# MotorBoardPrototyp4_polyfuse.net
KiCad netlist of a schematic drawn in EAGLE
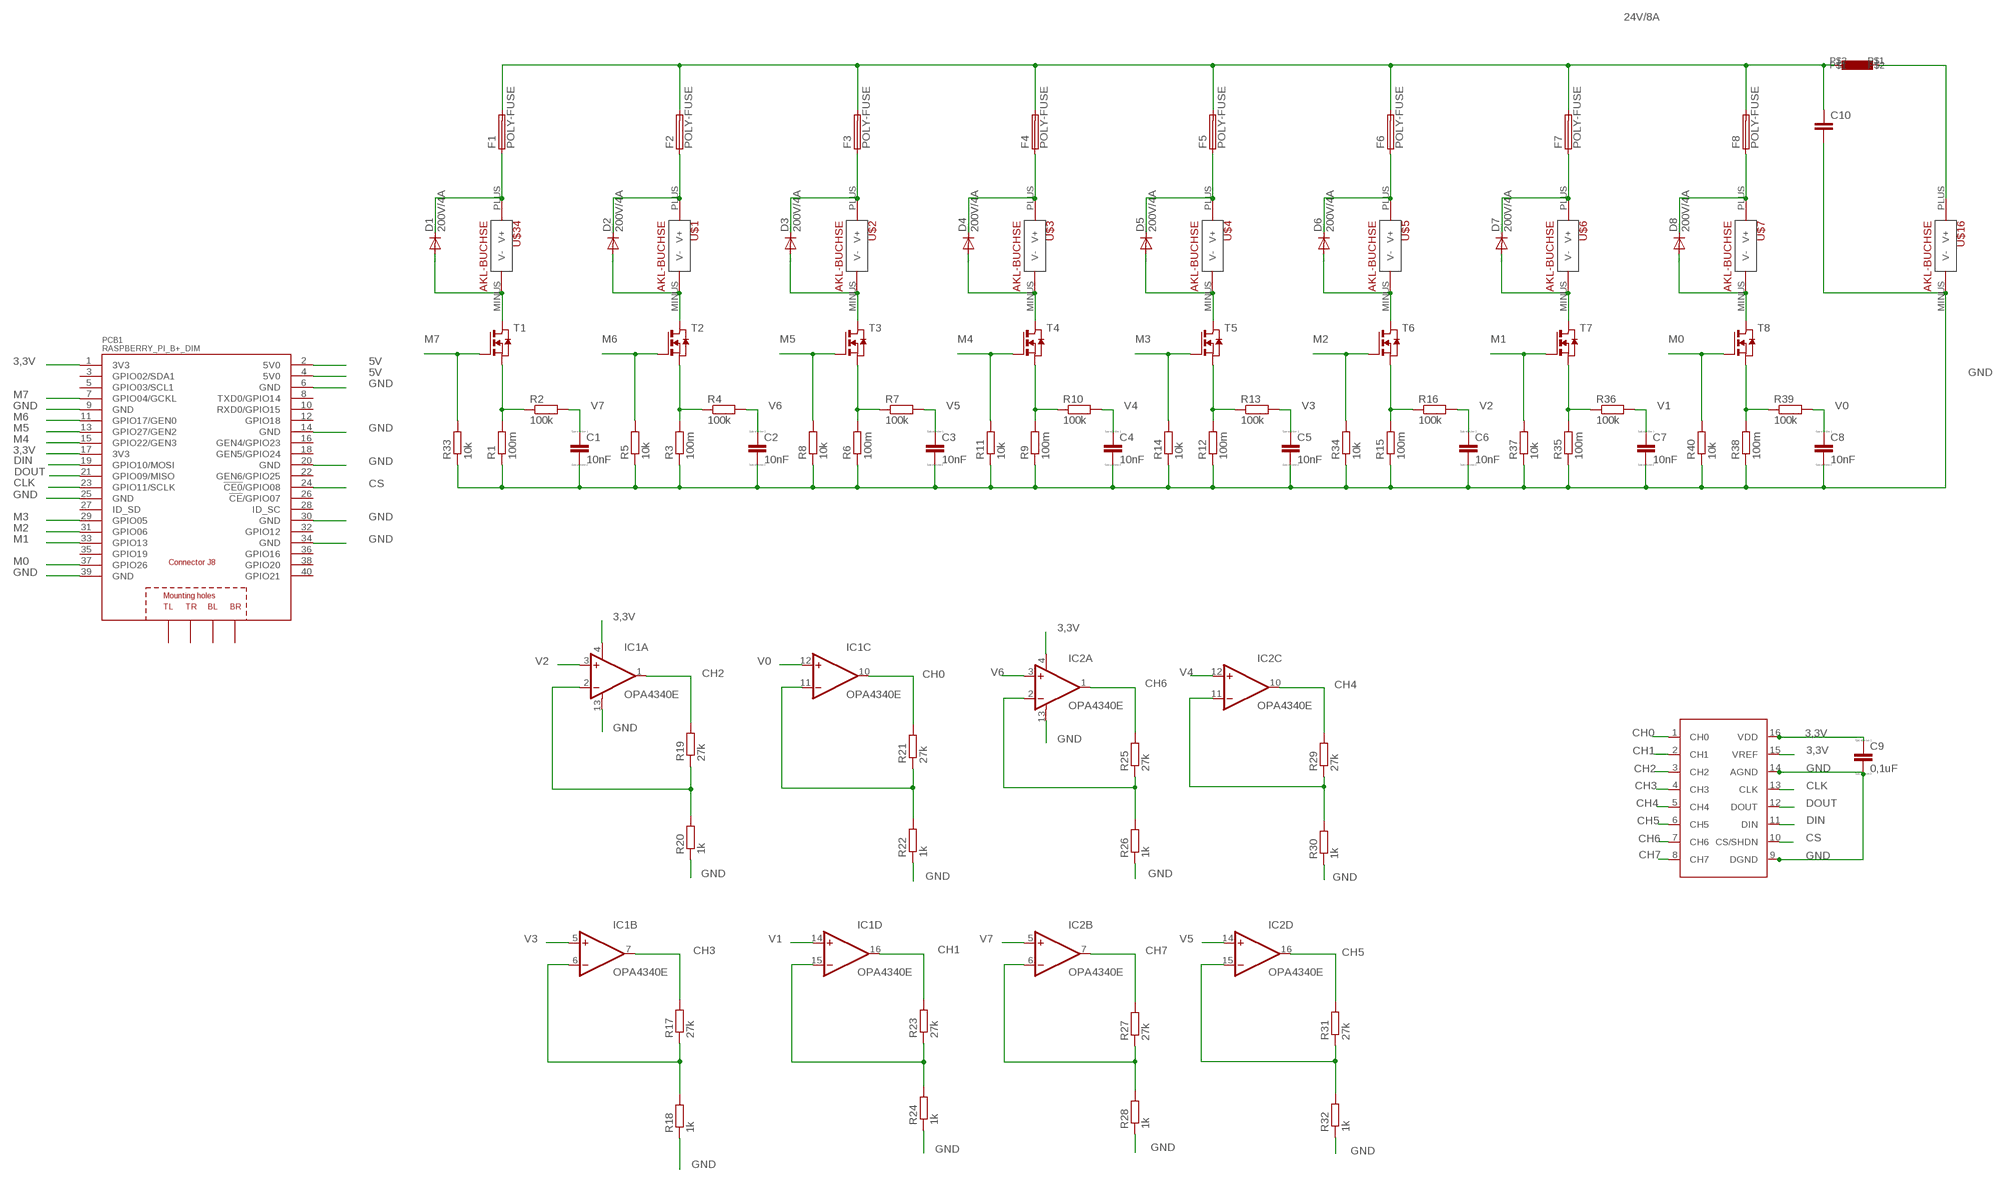
[diagram p0: schematic, sheet 1]

(export (version "E")
  (design (tool "Eeschema 10.0.6"))
  (components
    (comp (ref "C1")
      (value "10nF")
      (footprint "eagle-import:C0805")
      (libsource (lib "eagle-import") (part "C"))
    )
    (comp (ref "C2")
      (value "10nF")
      (footprint "eagle-import:C0805")
      (libsource (lib "eagle-import") (part "C"))
    )
    (comp (ref "C3")
      (value "10nF")
      (footprint "eagle-import:C0805")
      (libsource (lib "eagle-import") (part "C"))
    )
    (comp (ref "C4")
      (value "10nF")
      (footprint "eagle-import:C0805")
      (libsource (lib "eagle-import") (part "C"))
    )
    (comp (ref "C5")
      (value "10nF")
      (footprint "eagle-import:C0805")
      (libsource (lib "eagle-import") (part "C"))
    )
    (comp (ref "C6")
      (value "10nF")
      (footprint "eagle-import:C0805")
      (libsource (lib "eagle-import") (part "C"))
    )
    (comp (ref "C7")
      (value "10nF")
      (footprint "eagle-import:C0805")
      (libsource (lib "eagle-import") (part "C"))
    )
    (comp (ref "C8")
      (value "10nF")
      (footprint "eagle-import:C0805")
      (libsource (lib "eagle-import") (part "C"))
    )
    (comp (ref "C9")
      (value "0,1uF")
      (footprint "eagle-import:C0805")
      (libsource (lib "eagle-import") (part "C"))
    )
    (comp (ref "C10")
      (value "C-EUC1812")
      (footprint "eagle-import:C1812")
      (libsource (lib "eagle-import") (part "C-EUC1812"))
    )
    (comp (ref "D1")
      (value "200V/4A")
      (footprint "eagle-import:DO214AA")
      (libsource (lib "eagle-import") (part "DIODE-DO214AA"))
    )
    (comp (ref "D2")
      (value "200V/4A")
      (footprint "eagle-import:DO214AA")
      (libsource (lib "eagle-import") (part "DIODE-DO214AA"))
    )
    (comp (ref "D3")
      (value "200V/4A")
      (footprint "eagle-import:DO214AA")
      (libsource (lib "eagle-import") (part "DIODE-DO214AA"))
    )
    (comp (ref "D4")
      (value "200V/4A")
      (footprint "eagle-import:DO214AA")
      (libsource (lib "eagle-import") (part "DIODE-DO214AA"))
    )
    (comp (ref "D5")
      (value "200V/4A")
      (footprint "eagle-import:DO214AA")
      (libsource (lib "eagle-import") (part "DIODE-DO214AA"))
    )
    (comp (ref "D6")
      (value "200V/4A")
      (footprint "eagle-import:DO214AA")
      (libsource (lib "eagle-import") (part "DIODE-DO214AA"))
    )
    (comp (ref "D7")
      (value "200V/4A")
      (footprint "eagle-import:DO214AA")
      (libsource (lib "eagle-import") (part "DIODE-DO214AA"))
    )
    (comp (ref "D8")
      (value "200V/4A")
      (footprint "eagle-import:DO214AA")
      (libsource (lib "eagle-import") (part "DIODE-DO214AA"))
    )
    (comp (ref "F1")
      (value "POLY-FUSE")
      (footprint "eagle-import:1812L050")
      (libsource (lib "eagle-import") (part "POLY-FUSE"))
    )
    (comp (ref "F2")
      (value "POLY-FUSE")
      (footprint "eagle-import:1812L050")
      (libsource (lib "eagle-import") (part "POLY-FUSE"))
    )
    (comp (ref "F3")
      (value "POLY-FUSE")
      (footprint "eagle-import:1812L050")
      (libsource (lib "eagle-import") (part "POLY-FUSE"))
    )
    (comp (ref "F4")
      (value "POLY-FUSE")
      (footprint "eagle-import:1812L050")
      (libsource (lib "eagle-import") (part "POLY-FUSE"))
    )
    (comp (ref "F5")
      (value "POLY-FUSE")
      (footprint "eagle-import:1812L050")
      (libsource (lib "eagle-import") (part "POLY-FUSE"))
    )
    (comp (ref "F6")
      (value "POLY-FUSE")
      (footprint "eagle-import:1812L050")
      (libsource (lib "eagle-import") (part "POLY-FUSE"))
    )
    (comp (ref "F7")
      (value "POLY-FUSE")
      (footprint "eagle-import:1812L050")
      (libsource (lib "eagle-import") (part "POLY-FUSE"))
    )
    (comp (ref "F8")
      (value "POLY-FUSE")
      (footprint "eagle-import:1812L050")
      (libsource (lib "eagle-import") (part "POLY-FUSE"))
    )
    (comp (ref "IC1")
      (value "OPA4340E")
      (footprint "eagle-import:SSOP16BU")
      (fields (field (name "MPN") "OPA4340EA/250G4"))
      (libsource (lib "eagle-import") (part "OPA4340E"))
    )
    (comp (ref "IC2")
      (value "OPA4340E")
      (footprint "eagle-import:SSOP16BU")
      (fields (field (name "MPN") "OPA4340EA/250G4"))
      (libsource (lib "eagle-import") (part "OPA4340E"))
    )
    (comp (ref "L1")
      (value "MPI4040")
      (footprint "eagle-import:4040")
      (libsource (lib "eagle-import") (part "MPI4040"))
    )
    (comp (ref "PCB1")
      (value "RASPBERRY_PI_B+_DIM")
      (footprint "eagle-import:RASPBERRY_PI_BPLUS_DIM")
      (libsource (lib "eagle-import") (part "RASPBERRY_PI_B+_DIM"))
    )
    (comp (ref "R1")
      (value "100m")
      (footprint "eagle-import:R0805")
      (libsource (lib "eagle-import") (part "R-EU_R0805"))
    )
    (comp (ref "R2")
      (value "100k")
      (footprint "eagle-import:R0805")
      (libsource (lib "eagle-import") (part "R-EU_R0805"))
    )
    (comp (ref "R3")
      (value "100m")
      (footprint "eagle-import:R0805")
      (libsource (lib "eagle-import") (part "R-EU_R0805"))
    )
    (comp (ref "R4")
      (value "100k")
      (footprint "eagle-import:R0805")
      (libsource (lib "eagle-import") (part "R-EU_R0805"))
    )
    (comp (ref "R5")
      (value "10k")
      (footprint "eagle-import:R0805")
      (libsource (lib "eagle-import") (part "R-EU_R0805"))
    )
    (comp (ref "R6")
      (value "100m")
      (footprint "eagle-import:R0805")
      (libsource (lib "eagle-import") (part "R-EU_R0805"))
    )
    (comp (ref "R7")
      (value "100k")
      (footprint "eagle-import:R0805")
      (libsource (lib "eagle-import") (part "R-EU_R0805"))
    )
    (comp (ref "R8")
      (value "10k")
      (footprint "eagle-import:R0805")
      (libsource (lib "eagle-import") (part "R-EU_R0805"))
    )
    (comp (ref "R9")
      (value "100m")
      (footprint "eagle-import:R0805")
      (libsource (lib "eagle-import") (part "R-EU_R0805"))
    )
    (comp (ref "R10")
      (value "100k")
      (footprint "eagle-import:R0805")
      (libsource (lib "eagle-import") (part "R-EU_R0805"))
    )
    (comp (ref "R11")
      (value "10k")
      (footprint "eagle-import:R0805")
      (libsource (lib "eagle-import") (part "R-EU_R0805"))
    )
    (comp (ref "R12")
      (value "100m")
      (footprint "eagle-import:R0805")
      (libsource (lib "eagle-import") (part "R-EU_R0805"))
    )
    (comp (ref "R13")
      (value "100k")
      (footprint "eagle-import:R0805")
      (libsource (lib "eagle-import") (part "R-EU_R0805"))
    )
    (comp (ref "R14")
      (value "10k")
      (footprint "eagle-import:R0805")
      (libsource (lib "eagle-import") (part "R-EU_R0805"))
    )
    (comp (ref "R15")
      (value "100m")
      (footprint "eagle-import:R0805")
      (libsource (lib "eagle-import") (part "R-EU_R0805"))
    )
    (comp (ref "R16")
      (value "100k")
      (footprint "eagle-import:R0805")
      (libsource (lib "eagle-import") (part "R-EU_R0805"))
    )
    (comp (ref "R17")
      (value "27k")
      (footprint "eagle-import:R0805")
      (libsource (lib "eagle-import") (part "R-EU_R0805"))
    )
    (comp (ref "R18")
      (value "1k")
      (footprint "eagle-import:R0805")
      (libsource (lib "eagle-import") (part "R-EU_R0805"))
    )
    (comp (ref "R19")
      (value "27k")
      (footprint "eagle-import:R0805")
      (libsource (lib "eagle-import") (part "R-EU_R0805"))
    )
    (comp (ref "R20")
      (value "1k")
      (footprint "eagle-import:R0805")
      (libsource (lib "eagle-import") (part "R-EU_R0805"))
    )
    (comp (ref "R21")
      (value "27k")
      (footprint "eagle-import:R0805")
      (libsource (lib "eagle-import") (part "R-EU_R0805"))
    )
    (comp (ref "R22")
      (value "1k")
      (footprint "eagle-import:R0805")
      (libsource (lib "eagle-import") (part "R-EU_R0805"))
    )
    (comp (ref "R23")
      (value "27k")
      (footprint "eagle-import:R0805")
      (libsource (lib "eagle-import") (part "R-EU_R0805"))
    )
    (comp (ref "R24")
      (value "1k")
      (footprint "eagle-import:R0805")
      (libsource (lib "eagle-import") (part "R-EU_R0805"))
    )
    (comp (ref "R25")
      (value "27k")
      (footprint "eagle-import:R0805")
      (libsource (lib "eagle-import") (part "R-EU_R0805"))
    )
    (comp (ref "R26")
      (value "1k")
      (footprint "eagle-import:R0805")
      (libsource (lib "eagle-import") (part "R-EU_R0805"))
    )
    (comp (ref "R27")
      (value "27k")
      (footprint "eagle-import:R0805")
      (libsource (lib "eagle-import") (part "R-EU_R0805"))
    )
    (comp (ref "R28")
      (value "1k")
      (footprint "eagle-import:R0805")
      (libsource (lib "eagle-import") (part "R-EU_R0805"))
    )
    (comp (ref "R29")
      (value "27k")
      (footprint "eagle-import:R0805")
      (libsource (lib "eagle-import") (part "R-EU_R0805"))
    )
    (comp (ref "R30")
      (value "1k")
      (footprint "eagle-import:R0805")
      (libsource (lib "eagle-import") (part "R-EU_R0805"))
    )
    (comp (ref "R31")
      (value "27k")
      (footprint "eagle-import:R0805")
      (libsource (lib "eagle-import") (part "R-EU_R0805"))
    )
    (comp (ref "R32")
      (value "1k")
      (footprint "eagle-import:R0805")
      (libsource (lib "eagle-import") (part "R-EU_R0805"))
    )
    (comp (ref "R33")
      (value "10k")
      (footprint "eagle-import:R0805")
      (libsource (lib "eagle-import") (part "R-EU_R0805"))
    )
    (comp (ref "R34")
      (value "10k")
      (footprint "eagle-import:R0805")
      (libsource (lib "eagle-import") (part "R-EU_R0805"))
    )
    (comp (ref "R35")
      (value "100m")
      (footprint "eagle-import:R0805")
      (libsource (lib "eagle-import") (part "R-EU_R0805"))
    )
    (comp (ref "R36")
      (value "100k")
      (footprint "eagle-import:R0805")
      (libsource (lib "eagle-import") (part "R-EU_R0805"))
    )
    (comp (ref "R37")
      (value "10k")
      (footprint "eagle-import:R0805")
      (libsource (lib "eagle-import") (part "R-EU_R0805"))
    )
    (comp (ref "R38")
      (value "100m")
      (footprint "eagle-import:R0805")
      (libsource (lib "eagle-import") (part "R-EU_R0805"))
    )
    (comp (ref "R39")
      (value "100k")
      (footprint "eagle-import:R0805")
      (libsource (lib "eagle-import") (part "R-EU_R0805"))
    )
    (comp (ref "R40")
      (value "10k")
      (footprint "eagle-import:R0805")
      (libsource (lib "eagle-import") (part "R-EU_R0805"))
    )
    (comp (ref "T1")
      (value "NMOSSOT23")
      (footprint "eagle-import:SOT-23")
      (libsource (lib "eagle-import") (part "NMOSSOT23"))
    )
    (comp (ref "T2")
      (value "NMOSSOT23")
      (footprint "eagle-import:SOT-23")
      (libsource (lib "eagle-import") (part "NMOSSOT23"))
    )
    (comp (ref "T3")
      (value "NMOSSOT23")
      (footprint "eagle-import:SOT-23")
      (libsource (lib "eagle-import") (part "NMOSSOT23"))
    )
    (comp (ref "T4")
      (value "NMOSSOT23")
      (footprint "eagle-import:SOT-23")
      (libsource (lib "eagle-import") (part "NMOSSOT23"))
    )
    (comp (ref "T5")
      (value "NMOSSOT23")
      (footprint "eagle-import:SOT-23")
      (libsource (lib "eagle-import") (part "NMOSSOT23"))
    )
    (comp (ref "T6")
      (value "NMOSSOT23")
      (footprint "eagle-import:SOT-23")
      (libsource (lib "eagle-import") (part "NMOSSOT23"))
    )
    (comp (ref "T7")
      (value "NMOSSOT23")
      (footprint "eagle-import:SOT-23")
      (libsource (lib "eagle-import") (part "NMOSSOT23"))
    )
    (comp (ref "T8")
      (value "NMOSSOT23")
      (footprint "eagle-import:SOT-23")
      (libsource (lib "eagle-import") (part "NMOSSOT23"))
    )
    (comp (ref "U$1")
      (value "AKL-BUCHSE")
      (footprint "eagle-import:AKL-BUCHSE")
      (libsource (lib "eagle-import") (part "AKL-BUCHSE"))
    )
    (comp (ref "U$2")
      (value "AKL-BUCHSE")
      (footprint "eagle-import:AKL-BUCHSE")
      (libsource (lib "eagle-import") (part "AKL-BUCHSE"))
    )
    (comp (ref "U$3")
      (value "AKL-BUCHSE")
      (footprint "eagle-import:AKL-BUCHSE")
      (libsource (lib "eagle-import") (part "AKL-BUCHSE"))
    )
    (comp (ref "U$4")
      (value "AKL-BUCHSE")
      (footprint "eagle-import:AKL-BUCHSE")
      (libsource (lib "eagle-import") (part "AKL-BUCHSE"))
    )
    (comp (ref "U$5")
      (value "AKL-BUCHSE")
      (footprint "eagle-import:AKL-BUCHSE")
      (libsource (lib "eagle-import") (part "AKL-BUCHSE"))
    )
    (comp (ref "U$6")
      (value "AKL-BUCHSE")
      (footprint "eagle-import:AKL-BUCHSE")
      (libsource (lib "eagle-import") (part "AKL-BUCHSE"))
    )
    (comp (ref "U$7")
      (value "AKL-BUCHSE")
      (footprint "eagle-import:AKL-BUCHSE")
      (libsource (lib "eagle-import") (part "AKL-BUCHSE"))
    )
    (comp (ref "U$16")
      (value "AKL-BUCHSE")
      (footprint "eagle-import:AKL-BUCHSE")
      (libsource (lib "eagle-import") (part "AKL-BUCHSE"))
    )
    (comp (ref "U$34")
      (value "AKL-BUCHSE")
      (footprint "eagle-import:AKL-BUCHSE")
      (libsource (lib "eagle-import") (part "AKL-BUCHSE"))
    )
    (comp (ref "U$58")
      (value "MCP3008SO16")
      (footprint "eagle-import:SO16")
      (libsource (lib "eagle-import") (part "MCP3008SO16"))
    )
  )
  (nets
    (net (code "1") (name "/3,3V") (class "Default")
      (node (ref "C9") (pin "1") (pinfunction "1_1") (pintype "passive"))
      (node (ref "IC1") (pin "4") (pinfunction "V+_4") (pintype "power_in"))
      (node (ref "IC2") (pin "4") (pinfunction "V+_4") (pintype "power_in"))
      (node (ref "PCB1") (pin "1") (pinfunction "3V3_1") (pintype "power_in"))
      (node (ref "PCB1") (pin "17") (pinfunction "3V3_17") (pintype "power_in"))
      (node (ref "U$58") (pin "15") (pinfunction "VREF_15") (pintype "bidirectional"))
      (node (ref "U$58") (pin "16") (pinfunction "VDD_16") (pintype "bidirectional"))
    )
    (net (code "2") (name "/5V") (class "Default")
      (node (ref "PCB1") (pin "2") (pinfunction "5V0_2") (pintype "power_in"))
      (node (ref "PCB1") (pin "4") (pinfunction "5V0_4") (pintype "power_in"))
    )
    (net (code "3") (name "/24V{slash}8A") (class "Default")
      (node (ref "C10") (pin "1") (pinfunction "1_1") (pintype "passive"))
      (node (ref "F1") (pin "P$2") (pinfunction "2_P$2") (pintype "passive"))
      (node (ref "F2") (pin "P$2") (pinfunction "2_P$2") (pintype "passive"))
      (node (ref "F3") (pin "P$2") (pinfunction "2_P$2") (pintype "passive"))
      (node (ref "F4") (pin "P$2") (pinfunction "2_P$2") (pintype "passive"))
      (node (ref "F5") (pin "P$2") (pinfunction "2_P$2") (pintype "passive"))
      (node (ref "F6") (pin "P$2") (pinfunction "2_P$2") (pintype "passive"))
      (node (ref "F7") (pin "P$2") (pinfunction "2_P$2") (pintype "passive"))
      (node (ref "F8") (pin "P$2") (pinfunction "2_P$2") (pintype "passive"))
      (node (ref "L1") (pin "P$2") (pinfunction "P$2_P$2") (pintype "bidirectional"))
    )
    (net (code "4") (name "/CH0") (class "Default")
      (node (ref "IC1") (pin "10") (pinfunction "OUT_10") (pintype "output"))
      (node (ref "R21") (pin "2") (pinfunction "2_2") (pintype "passive"))
      (node (ref "U$58") (pin "1") (pinfunction "CH0_1") (pintype "bidirectional"))
    )
    (net (code "5") (name "/CH1") (class "Default")
      (node (ref "IC1") (pin "16") (pinfunction "OUT_16") (pintype "output"))
      (node (ref "R23") (pin "2") (pinfunction "2_2") (pintype "passive"))
      (node (ref "U$58") (pin "2") (pinfunction "CH1_2") (pintype "bidirectional"))
    )
    (net (code "6") (name "/CH2") (class "Default")
      (node (ref "IC1") (pin "1") (pinfunction "OUT_1") (pintype "output"))
      (node (ref "R19") (pin "2") (pinfunction "2_2") (pintype "passive"))
      (node (ref "U$58") (pin "3") (pinfunction "CH2_3") (pintype "bidirectional"))
    )
    (net (code "7") (name "/CH3") (class "Default")
      (node (ref "IC1") (pin "7") (pinfunction "OUT_7") (pintype "output"))
      (node (ref "R17") (pin "2") (pinfunction "2_2") (pintype "passive"))
      (node (ref "U$58") (pin "4") (pinfunction "CH3_4") (pintype "bidirectional"))
    )
    (net (code "8") (name "/CH4") (class "Default")
      (node (ref "IC2") (pin "10") (pinfunction "OUT_10") (pintype "output"))
      (node (ref "R29") (pin "2") (pinfunction "2_2") (pintype "passive"))
      (node (ref "U$58") (pin "5") (pinfunction "CH4_5") (pintype "bidirectional"))
    )
    (net (code "9") (name "/CH5") (class "Default")
      (node (ref "IC2") (pin "16") (pinfunction "OUT_16") (pintype "output"))
      (node (ref "R31") (pin "2") (pinfunction "2_2") (pintype "passive"))
      (node (ref "U$58") (pin "6") (pinfunction "CH5_6") (pintype "bidirectional"))
    )
    (net (code "10") (name "/CH6") (class "Default")
      (node (ref "IC2") (pin "1") (pinfunction "OUT_1") (pintype "output"))
      (node (ref "R25") (pin "2") (pinfunction "2_2") (pintype "passive"))
      (node (ref "U$58") (pin "7") (pinfunction "CH6_7") (pintype "bidirectional"))
    )
    (net (code "11") (name "/CH7") (class "Default")
      (node (ref "IC2") (pin "7") (pinfunction "OUT_7") (pintype "output"))
      (node (ref "R27") (pin "2") (pinfunction "2_2") (pintype "passive"))
      (node (ref "U$58") (pin "8") (pinfunction "CH7_8") (pintype "bidirectional"))
    )
    (net (code "12") (name "/CLK") (class "Default")
      (node (ref "PCB1") (pin "23") (pinfunction "GPIO11/SCLK_23") (pintype "bidirectional"))
      (node (ref "U$58") (pin "13") (pinfunction "CLK_13") (pintype "bidirectional"))
    )
    (net (code "13") (name "/CS") (class "Default")
      (node (ref "PCB1") (pin "24") (pinfunction "~{CE0}/GPIO08_24") (pintype "bidirectional"))
      (node (ref "U$58") (pin "10") (pinfunction "CS/SHDN_10") (pintype "bidirectional"))
    )
    (net (code "14") (name "/DIN") (class "Default")
      (node (ref "PCB1") (pin "19") (pinfunction "GPIO10/MOSI_19") (pintype "bidirectional"))
      (node (ref "U$58") (pin "11") (pinfunction "DIN_11") (pintype "bidirectional"))
    )
    (net (code "15") (name "/DOUT") (class "Default")
      (node (ref "PCB1") (pin "21") (pinfunction "GPIO09/MISO_21") (pintype "bidirectional"))
      (node (ref "U$58") (pin "12") (pinfunction "DOUT_12") (pintype "bidirectional"))
    )
    (net (code "16") (name "/GND") (class "Default")
      (node (ref "C1") (pin "2") (pinfunction "2_2") (pintype "passive"))
      (node (ref "C10") (pin "2") (pinfunction "2_2") (pintype "passive"))
      (node (ref "C2") (pin "2") (pinfunction "2_2") (pintype "passive"))
      (node (ref "C3") (pin "2") (pinfunction "2_2") (pintype "passive"))
      (node (ref "C4") (pin "2") (pinfunction "2_2") (pintype "passive"))
      (node (ref "C5") (pin "2") (pinfunction "2_2") (pintype "passive"))
      (node (ref "C6") (pin "2") (pinfunction "2_2") (pintype "passive"))
      (node (ref "C7") (pin "2") (pinfunction "2_2") (pintype "passive"))
      (node (ref "C8") (pin "2") (pinfunction "2_2") (pintype "passive"))
      (node (ref "C9") (pin "2") (pinfunction "2_2") (pintype "passive"))
      (node (ref "IC1") (pin "13") (pinfunction "V-_13") (pintype "power_in"))
      (node (ref "IC2") (pin "13") (pinfunction "V-_13") (pintype "power_in"))
      (node (ref "PCB1") (pin "14") (pinfunction "GND_14") (pintype "power_in"))
      (node (ref "PCB1") (pin "20") (pinfunction "GND_20") (pintype "power_in"))
      (node (ref "PCB1") (pin "25") (pinfunction "GND_25") (pintype "power_in"))
      (node (ref "PCB1") (pin "30") (pinfunction "GND_30") (pintype "power_in"))
      (node (ref "PCB1") (pin "34") (pinfunction "GND_34") (pintype "power_in"))
      (node (ref "PCB1") (pin "39") (pinfunction "GND_39") (pintype "power_in"))
      (node (ref "PCB1") (pin "6") (pinfunction "GND_6") (pintype "power_in"))
      (node (ref "PCB1") (pin "9") (pinfunction "GND_9") (pintype "power_in"))
      (node (ref "R1") (pin "1") (pinfunction "1_1") (pintype "passive"))
      (node (ref "R11") (pin "1") (pinfunction "1_1") (pintype "passive"))
      (node (ref "R12") (pin "1") (pinfunction "1_1") (pintype "passive"))
      (node (ref "R14") (pin "1") (pinfunction "1_1") (pintype "passive"))
      (node (ref "R15") (pin "1") (pinfunction "1_1") (pintype "passive"))
      (node (ref "R18") (pin "1") (pinfunction "1_1") (pintype "passive"))
      (node (ref "R20") (pin "1") (pinfunction "1_1") (pintype "passive"))
      (node (ref "R22") (pin "1") (pinfunction "1_1") (pintype "passive"))
      (node (ref "R24") (pin "1") (pinfunction "1_1") (pintype "passive"))
      (node (ref "R26") (pin "1") (pinfunction "1_1") (pintype "passive"))
      (node (ref "R28") (pin "1") (pinfunction "1_1") (pintype "passive"))
      (node (ref "R3") (pin "1") (pinfunction "1_1") (pintype "passive"))
      (node (ref "R30") (pin "1") (pinfunction "1_1") (pintype "passive"))
      (node (ref "R32") (pin "1") (pinfunction "1_1") (pintype "passive"))
      (node (ref "R33") (pin "1") (pinfunction "1_1") (pintype "passive"))
      (node (ref "R34") (pin "1") (pinfunction "1_1") (pintype "passive"))
      (node (ref "R35") (pin "1") (pinfunction "1_1") (pintype "passive"))
      (node (ref "R37") (pin "1") (pinfunction "1_1") (pintype "passive"))
      (node (ref "R38") (pin "1") (pinfunction "1_1") (pintype "passive"))
      (node (ref "R40") (pin "1") (pinfunction "1_1") (pintype "passive"))
      (node (ref "R5") (pin "1") (pinfunction "1_1") (pintype "passive"))
      (node (ref "R6") (pin "1") (pinfunction "1_1") (pintype "passive"))
      (node (ref "R8") (pin "1") (pinfunction "1_1") (pintype "passive"))
      (node (ref "R9") (pin "1") (pinfunction "1_1") (pintype "passive"))
      (node (ref "U$16") (pin "MINUS") (pinfunction "V-_MINUS") (pintype "bidirectional"))
      (node (ref "U$58") (pin "14") (pinfunction "AGND_14") (pintype "bidirectional"))
      (node (ref "U$58") (pin "9") (pinfunction "DGND_9") (pintype "bidirectional"))
    )
    (net (code "17") (name "/M0") (class "Default")
      (node (ref "PCB1") (pin "37") (pinfunction "GPIO26_37") (pintype "bidirectional"))
      (node (ref "R40") (pin "2") (pinfunction "2_2") (pintype "passive"))
      (node (ref "T8") (pin "3") (pinfunction "G_3") (pintype "passive"))
    )
    (net (code "18") (name "/M1") (class "Default")
      (node (ref "PCB1") (pin "33") (pinfunction "GPIO13_33") (pintype "bidirectional"))
      (node (ref "R37") (pin "2") (pinfunction "2_2") (pintype "passive"))
      (node (ref "T7") (pin "3") (pinfunction "G_3") (pintype "passive"))
    )
    (net (code "19") (name "/M2") (class "Default")
      (node (ref "PCB1") (pin "31") (pinfunction "GPIO06_31") (pintype "bidirectional"))
      (node (ref "R34") (pin "2") (pinfunction "2_2") (pintype "passive"))
      (node (ref "T6") (pin "3") (pinfunction "G_3") (pintype "passive"))
    )
    (net (code "20") (name "/M3") (class "Default")
      (node (ref "PCB1") (pin "29") (pinfunction "GPIO05_29") (pintype "bidirectional"))
      (node (ref "R14") (pin "2") (pinfunction "2_2") (pintype "passive"))
      (node (ref "T5") (pin "3") (pinfunction "G_3") (pintype "passive"))
    )
    (net (code "21") (name "/M4") (class "Default")
      (node (ref "PCB1") (pin "15") (pinfunction "GPIO22/GEN3_15") (pintype "bidirectional"))
      (node (ref "R11") (pin "2") (pinfunction "2_2") (pintype "passive"))
      (node (ref "T4") (pin "3") (pinfunction "G_3") (pintype "passive"))
    )
    (net (code "22") (name "/M5") (class "Default")
      (node (ref "PCB1") (pin "13") (pinfunction "GPIO27/GEN2_13") (pintype "bidirectional"))
      (node (ref "R8") (pin "2") (pinfunction "2_2") (pintype "passive"))
      (node (ref "T3") (pin "3") (pinfunction "G_3") (pintype "passive"))
    )
    (net (code "23") (name "/M6") (class "Default")
      (node (ref "PCB1") (pin "11") (pinfunction "GPIO17/GEN0_11") (pintype "bidirectional"))
      (node (ref "R5") (pin "2") (pinfunction "2_2") (pintype "passive"))
      (node (ref "T2") (pin "3") (pinfunction "G_3") (pintype "passive"))
    )
    (net (code "24") (name "/M7") (class "Default")
      (node (ref "PCB1") (pin "7") (pinfunction "GPIO04/GCKL_7") (pintype "bidirectional"))
      (node (ref "R33") (pin "2") (pinfunction "2_2") (pintype "passive"))
      (node (ref "T1") (pin "3") (pinfunction "G_3") (pintype "passive"))
    )
    (net (code "25") (name "/V0") (class "Default")
      (node (ref "C8") (pin "1") (pinfunction "1_1") (pintype "passive"))
      (node (ref "IC1") (pin "12") (pinfunction "+IN_12") (pintype "input"))
      (node (ref "R39") (pin "2") (pinfunction "2_2") (pintype "passive"))
    )
    (net (code "26") (name "/V1") (class "Default")
      (node (ref "C7") (pin "1") (pinfunction "1_1") (pintype "passive"))
      (node (ref "IC1") (pin "14") (pinfunction "+IN_14") (pintype "input"))
      (node (ref "R36") (pin "2") (pinfunction "2_2") (pintype "passive"))
    )
    (net (code "27") (name "/V2") (class "Default")
      (node (ref "C6") (pin "1") (pinfunction "1_1") (pintype "passive"))
      (node (ref "IC1") (pin "3") (pinfunction "+IN_3") (pintype "input"))
      (node (ref "R16") (pin "2") (pinfunction "2_2") (pintype "passive"))
    )
    (net (code "28") (name "/V3") (class "Default")
      (node (ref "C5") (pin "1") (pinfunction "1_1") (pintype "passive"))
      (node (ref "IC1") (pin "5") (pinfunction "+IN_5") (pintype "input"))
      (node (ref "R13") (pin "2") (pinfunction "2_2") (pintype "passive"))
    )
    (net (code "29") (name "/V4") (class "Default")
      (node (ref "C4") (pin "1") (pinfunction "1_1") (pintype "passive"))
      (node (ref "IC2") (pin "12") (pinfunction "+IN_12") (pintype "input"))
      (node (ref "R10") (pin "2") (pinfunction "2_2") (pintype "passive"))
    )
    (net (code "30") (name "/V5") (class "Default")
      (node (ref "C3") (pin "1") (pinfunction "1_1") (pintype "passive"))
      (node (ref "IC2") (pin "14") (pinfunction "+IN_14") (pintype "input"))
      (node (ref "R7") (pin "2") (pinfunction "2_2") (pintype "passive"))
    )
    (net (code "31") (name "/V6") (class "Default")
      (node (ref "C2") (pin "1") (pinfunction "1_1") (pintype "passive"))
      (node (ref "IC2") (pin "3") (pinfunction "+IN_3") (pintype "input"))
      (node (ref "R4") (pin "2") (pinfunction "2_2") (pintype "passive"))
    )
    (net (code "32") (name "/V7") (class "Default")
      (node (ref "C1") (pin "1") (pinfunction "1_1") (pintype "passive"))
      (node (ref "IC2") (pin "5") (pinfunction "+IN_5") (pintype "input"))
      (node (ref "R2") (pin "2") (pinfunction "2_2") (pintype "passive"))
    )
    (net (code "33") (name "Net-(F1-1)") (class "Default")
      (node (ref "D1") (pin "C") (pinfunction "C_C") (pintype "passive"))
      (node (ref "F1") (pin "P$1") (pinfunction "1_P$1") (pintype "passive"))
      (node (ref "U$34") (pin "PLUS") (pinfunction "V+_PLUS") (pintype "bidirectional"))
    )
    (net (code "34") (name "Net-(F2-1)") (class "Default")
      (node (ref "D2") (pin "C") (pinfunction "C_C") (pintype "passive"))
      (node (ref "F2") (pin "P$1") (pinfunction "1_P$1") (pintype "passive"))
      (node (ref "U$1") (pin "PLUS") (pinfunction "V+_PLUS") (pintype "bidirectional"))
    )
    (net (code "35") (name "Net-(F3-1)") (class "Default")
      (node (ref "D3") (pin "C") (pinfunction "C_C") (pintype "passive"))
      (node (ref "F3") (pin "P$1") (pinfunction "1_P$1") (pintype "passive"))
      (node (ref "U$2") (pin "PLUS") (pinfunction "V+_PLUS") (pintype "bidirectional"))
    )
    (net (code "36") (name "Net-(F4-1)") (class "Default")
      (node (ref "D4") (pin "C") (pinfunction "C_C") (pintype "passive"))
      (node (ref "F4") (pin "P$1") (pinfunction "1_P$1") (pintype "passive"))
      (node (ref "U$3") (pin "PLUS") (pinfunction "V+_PLUS") (pintype "bidirectional"))
    )
    (net (code "37") (name "Net-(F5-1)") (class "Default")
      (node (ref "D5") (pin "C") (pinfunction "C_C") (pintype "passive"))
      (node (ref "F5") (pin "P$1") (pinfunction "1_P$1") (pintype "passive"))
      (node (ref "U$4") (pin "PLUS") (pinfunction "V+_PLUS") (pintype "bidirectional"))
    )
    (net (code "38") (name "Net-(F6-1)") (class "Default")
      (node (ref "D6") (pin "C") (pinfunction "C_C") (pintype "passive"))
      (node (ref "F6") (pin "P$1") (pinfunction "1_P$1") (pintype "passive"))
      (node (ref "U$5") (pin "PLUS") (pinfunction "V+_PLUS") (pintype "bidirectional"))
    )
    (net (code "39") (name "Net-(F7-1)") (class "Default")
      (node (ref "D7") (pin "C") (pinfunction "C_C") (pintype "passive"))
      (node (ref "F7") (pin "P$1") (pinfunction "1_P$1") (pintype "passive"))
      (node (ref "U$6") (pin "PLUS") (pinfunction "V+_PLUS") (pintype "bidirectional"))
    )
    (net (code "40") (name "Net-(F8-1)") (class "Default")
      (node (ref "D8") (pin "C") (pinfunction "C_C") (pintype "passive"))
      (node (ref "F8") (pin "P$1") (pinfunction "1_P$1") (pintype "passive"))
      (node (ref "U$7") (pin "PLUS") (pinfunction "V+_PLUS") (pintype "bidirectional"))
    )
    (net (code "41") (name "Net-(IC1A--IN)") (class "Default")
      (node (ref "IC1") (pin "2") (pinfunction "-IN_2") (pintype "input"))
      (node (ref "R19") (pin "1") (pinfunction "1_1") (pintype "passive"))
      (node (ref "R20") (pin "2") (pinfunction "2_2") (pintype "passive"))
    )
    (net (code "42") (name "Net-(IC1B--IN)") (class "Default")
      (node (ref "IC1") (pin "6") (pinfunction "-IN_6") (pintype "input"))
      (node (ref "R17") (pin "1") (pinfunction "1_1") (pintype "passive"))
      (node (ref "R18") (pin "2") (pinfunction "2_2") (pintype "passive"))
    )
    (net (code "43") (name "Net-(IC1C--IN)") (class "Default")
      (node (ref "IC1") (pin "11") (pinfunction "-IN_11") (pintype "input"))
      (node (ref "R21") (pin "1") (pinfunction "1_1") (pintype "passive"))
      (node (ref "R22") (pin "2") (pinfunction "2_2") (pintype "passive"))
    )
    (net (code "44") (name "Net-(IC1D--IN)") (class "Default")
      (node (ref "IC1") (pin "15") (pinfunction "-IN_15") (pintype "input"))
      (node (ref "R23") (pin "1") (pinfunction "1_1") (pintype "passive"))
      (node (ref "R24") (pin "2") (pinfunction "2_2") (pintype "passive"))
    )
    (net (code "45") (name "Net-(IC2A--IN)") (class "Default")
      (node (ref "IC2") (pin "2") (pinfunction "-IN_2") (pintype "input"))
      (node (ref "R25") (pin "1") (pinfunction "1_1") (pintype "passive"))
      (node (ref "R26") (pin "2") (pinfunction "2_2") (pintype "passive"))
    )
    (net (code "46") (name "Net-(IC2B--IN)") (class "Default")
      (node (ref "IC2") (pin "6") (pinfunction "-IN_6") (pintype "input"))
      (node (ref "R27") (pin "1") (pinfunction "1_1") (pintype "passive"))
      (node (ref "R28") (pin "2") (pinfunction "2_2") (pintype "passive"))
    )
    (net (code "47") (name "Net-(IC2C--IN)") (class "Default")
      (node (ref "IC2") (pin "11") (pinfunction "-IN_11") (pintype "input"))
      (node (ref "R29") (pin "1") (pinfunction "1_1") (pintype "passive"))
      (node (ref "R30") (pin "2") (pinfunction "2_2") (pintype "passive"))
    )
    (net (code "48") (name "Net-(IC2D--IN)") (class "Default")
      (node (ref "IC2") (pin "15") (pinfunction "-IN_15") (pintype "input"))
      (node (ref "R31") (pin "1") (pinfunction "1_1") (pintype "passive"))
      (node (ref "R32") (pin "2") (pinfunction "2_2") (pintype "passive"))
    )
    (net (code "49") (name "Net-(T1-D)") (class "Default")
      (node (ref "D1") (pin "A") (pinfunction "A_A") (pintype "passive"))
      (node (ref "T1") (pin "1") (pinfunction "D_1") (pintype "passive"))
      (node (ref "U$34") (pin "MINUS") (pinfunction "V-_MINUS") (pintype "bidirectional"))
    )
    (net (code "50") (name "Net-(T1-S)") (class "Default")
      (node (ref "R1") (pin "2") (pinfunction "2_2") (pintype "passive"))
      (node (ref "R2") (pin "1") (pinfunction "1_1") (pintype "passive"))
      (node (ref "T1") (pin "2") (pinfunction "S_2") (pintype "passive"))
    )
    (net (code "51") (name "Net-(T2-D)") (class "Default")
      (node (ref "D2") (pin "A") (pinfunction "A_A") (pintype "passive"))
      (node (ref "T2") (pin "1") (pinfunction "D_1") (pintype "passive"))
      (node (ref "U$1") (pin "MINUS") (pinfunction "V-_MINUS") (pintype "bidirectional"))
    )
    (net (code "52") (name "Net-(T2-S)") (class "Default")
      (node (ref "R3") (pin "2") (pinfunction "2_2") (pintype "passive"))
      (node (ref "R4") (pin "1") (pinfunction "1_1") (pintype "passive"))
      (node (ref "T2") (pin "2") (pinfunction "S_2") (pintype "passive"))
    )
    (net (code "53") (name "Net-(T3-D)") (class "Default")
      (node (ref "D3") (pin "A") (pinfunction "A_A") (pintype "passive"))
      (node (ref "T3") (pin "1") (pinfunction "D_1") (pintype "passive"))
      (node (ref "U$2") (pin "MINUS") (pinfunction "V-_MINUS") (pintype "bidirectional"))
    )
    (net (code "54") (name "Net-(T3-S)") (class "Default")
      (node (ref "R6") (pin "2") (pinfunction "2_2") (pintype "passive"))
      (node (ref "R7") (pin "1") (pinfunction "1_1") (pintype "passive"))
      (node (ref "T3") (pin "2") (pinfunction "S_2") (pintype "passive"))
    )
    (net (code "55") (name "Net-(T4-D)") (class "Default")
      (node (ref "D4") (pin "A") (pinfunction "A_A") (pintype "passive"))
      (node (ref "T4") (pin "1") (pinfunction "D_1") (pintype "passive"))
      (node (ref "U$3") (pin "MINUS") (pinfunction "V-_MINUS") (pintype "bidirectional"))
    )
    (net (code "56") (name "Net-(T4-S)") (class "Default")
      (node (ref "R10") (pin "1") (pinfunction "1_1") (pintype "passive"))
      (node (ref "R9") (pin "2") (pinfunction "2_2") (pintype "passive"))
      (node (ref "T4") (pin "2") (pinfunction "S_2") (pintype "passive"))
    )
    (net (code "57") (name "Net-(T5-D)") (class "Default")
      (node (ref "D5") (pin "A") (pinfunction "A_A") (pintype "passive"))
      (node (ref "T5") (pin "1") (pinfunction "D_1") (pintype "passive"))
      (node (ref "U$4") (pin "MINUS") (pinfunction "V-_MINUS") (pintype "bidirectional"))
    )
    (net (code "58") (name "Net-(T5-S)") (class "Default")
      (node (ref "R12") (pin "2") (pinfunction "2_2") (pintype "passive"))
      (node (ref "R13") (pin "1") (pinfunction "1_1") (pintype "passive"))
      (node (ref "T5") (pin "2") (pinfunction "S_2") (pintype "passive"))
    )
    (net (code "59") (name "Net-(T6-D)") (class "Default")
      (node (ref "D6") (pin "A") (pinfunction "A_A") (pintype "passive"))
      (node (ref "T6") (pin "1") (pinfunction "D_1") (pintype "passive"))
      (node (ref "U$5") (pin "MINUS") (pinfunction "V-_MINUS") (pintype "bidirectional"))
    )
    (net (code "60") (name "Net-(T6-S)") (class "Default")
      (node (ref "R15") (pin "2") (pinfunction "2_2") (pintype "passive"))
      (node (ref "R16") (pin "1") (pinfunction "1_1") (pintype "passive"))
      (node (ref "T6") (pin "2") (pinfunction "S_2") (pintype "passive"))
    )
    (net (code "61") (name "Net-(T7-D)") (class "Default")
      (node (ref "D7") (pin "A") (pinfunction "A_A") (pintype "passive"))
      (node (ref "T7") (pin "1") (pinfunction "D_1") (pintype "passive"))
      (node (ref "U$6") (pin "MINUS") (pinfunction "V-_MINUS") (pintype "bidirectional"))
    )
    (net (code "62") (name "Net-(T7-S)") (class "Default")
      (node (ref "R35") (pin "2") (pinfunction "2_2") (pintype "passive"))
      (node (ref "R36") (pin "1") (pinfunction "1_1") (pintype "passive"))
      (node (ref "T7") (pin "2") (pinfunction "S_2") (pintype "passive"))
    )
    (net (code "63") (name "Net-(T8-D)") (class "Default")
      (node (ref "D8") (pin "A") (pinfunction "A_A") (pintype "passive"))
      (node (ref "T8") (pin "1") (pinfunction "D_1") (pintype "passive"))
      (node (ref "U$7") (pin "MINUS") (pinfunction "V-_MINUS") (pintype "bidirectional"))
    )
    (net (code "64") (name "Net-(T8-S)") (class "Default")
      (node (ref "R38") (pin "2") (pinfunction "2_2") (pintype "passive"))
      (node (ref "R39") (pin "1") (pinfunction "1_1") (pintype "passive"))
      (node (ref "T8") (pin "2") (pinfunction "S_2") (pintype "passive"))
    )
    (net (code "65") (name "Net-(U$16-V+)") (class "Default")
      (node (ref "L1") (pin "P$1") (pinfunction "P$1_P$1") (pintype "bidirectional"))
      (node (ref "U$16") (pin "PLUS") (pinfunction "V+_PLUS") (pintype "bidirectional"))
    )
    (net (code "66") (name "unconnected-(PCB1-BL-PadPE_BL)") (class "Default")
      (node (ref "PCB1") (pin "PE_BL") (pinfunction "BL_PE_BL") (pintype "bidirectional"))
    )
    (net (code "67") (name "unconnected-(PCB1-BR-PadPE_BR)") (class "Default")
      (node (ref "PCB1") (pin "PE_BR") (pinfunction "BR_PE_BR") (pintype "bidirectional"))
    )
    (net (code "68") (name "unconnected-(PCB1-GEN4{slash}GPIO23-Pad16)") (class "Default")
      (node (ref "PCB1") (pin "16") (pinfunction "GEN4/GPIO23_16") (pintype "bidirectional"))
    )
    (net (code "69") (name "unconnected-(PCB1-GEN5{slash}GPIO24-Pad18)") (class "Default")
      (node (ref "PCB1") (pin "18") (pinfunction "GEN5/GPIO24_18") (pintype "bidirectional"))
    )
    (net (code "70") (name "unconnected-(PCB1-GEN6{slash}GPIO25-Pad22)") (class "Default")
      (node (ref "PCB1") (pin "22") (pinfunction "GEN6/GPIO25_22") (pintype "bidirectional"))
    )
    (net (code "71") (name "unconnected-(PCB1-GPIO02{slash}SDA1-Pad3)") (class "Default")
      (node (ref "PCB1") (pin "3") (pinfunction "GPIO02/SDA1_3") (pintype "bidirectional"))
    )
    (net (code "72") (name "unconnected-(PCB1-GPIO03{slash}SCL1-Pad5)") (class "Default")
      (node (ref "PCB1") (pin "5") (pinfunction "GPIO03/SCL1_5") (pintype "bidirectional"))
    )
    (net (code "73") (name "unconnected-(PCB1-GPIO12-Pad32)") (class "Default")
      (node (ref "PCB1") (pin "32") (pinfunction "GPIO12_32") (pintype "bidirectional"))
    )
    (net (code "74") (name "unconnected-(PCB1-GPIO16-Pad36)") (class "Default")
      (node (ref "PCB1") (pin "36") (pinfunction "GPIO16_36") (pintype "bidirectional"))
    )
    (net (code "75") (name "unconnected-(PCB1-GPIO18-Pad12)") (class "Default")
      (node (ref "PCB1") (pin "12") (pinfunction "GPIO18_12") (pintype "bidirectional"))
    )
    (net (code "76") (name "unconnected-(PCB1-GPIO19-Pad35)") (class "Default")
      (node (ref "PCB1") (pin "35") (pinfunction "GPIO19_35") (pintype "bidirectional"))
    )
    (net (code "77") (name "unconnected-(PCB1-GPIO20-Pad38)") (class "Default")
      (node (ref "PCB1") (pin "38") (pinfunction "GPIO20_38") (pintype "bidirectional"))
    )
    (net (code "78") (name "unconnected-(PCB1-GPIO21-Pad40)") (class "Default")
      (node (ref "PCB1") (pin "40") (pinfunction "GPIO21_40") (pintype "bidirectional"))
    )
    (net (code "79") (name "unconnected-(PCB1-ID_SC-Pad28)") (class "Default")
      (node (ref "PCB1") (pin "28") (pinfunction "ID_SC_28") (pintype "bidirectional"))
    )
    (net (code "80") (name "unconnected-(PCB1-ID_SD-Pad27)") (class "Default")
      (node (ref "PCB1") (pin "27") (pinfunction "ID_SD_27") (pintype "bidirectional"))
    )
    (net (code "81") (name "unconnected-(PCB1-RXD0{slash}GPIO15-Pad10)") (class "Default")
      (node (ref "PCB1") (pin "10") (pinfunction "RXD0/GPIO15_10") (pintype "bidirectional"))
    )
    (net (code "82") (name "unconnected-(PCB1-TL-PadPE_TL)") (class "Default")
      (node (ref "PCB1") (pin "PE_TL") (pinfunction "TL_PE_TL") (pintype "bidirectional"))
    )
    (net (code "83") (name "unconnected-(PCB1-TR-PadPE_TR)") (class "Default")
      (node (ref "PCB1") (pin "PE_TR") (pinfunction "TR_PE_TR") (pintype "bidirectional"))
    )
    (net (code "84") (name "unconnected-(PCB1-TXD0{slash}GPIO14-Pad8)") (class "Default")
      (node (ref "PCB1") (pin "8") (pinfunction "TXD0/GPIO14_8") (pintype "bidirectional"))
    )
    (net (code "85") (name "unconnected-(PCB1-~{CE}{slash}GPIO07-Pad26)") (class "Default")
      (node (ref "PCB1") (pin "26") (pinfunction "~{CE}/GPIO07_26") (pintype "bidirectional"))
    )
  )
)
